# Supply.net
KiCad netlist of a schematic drawn in Altium Designer
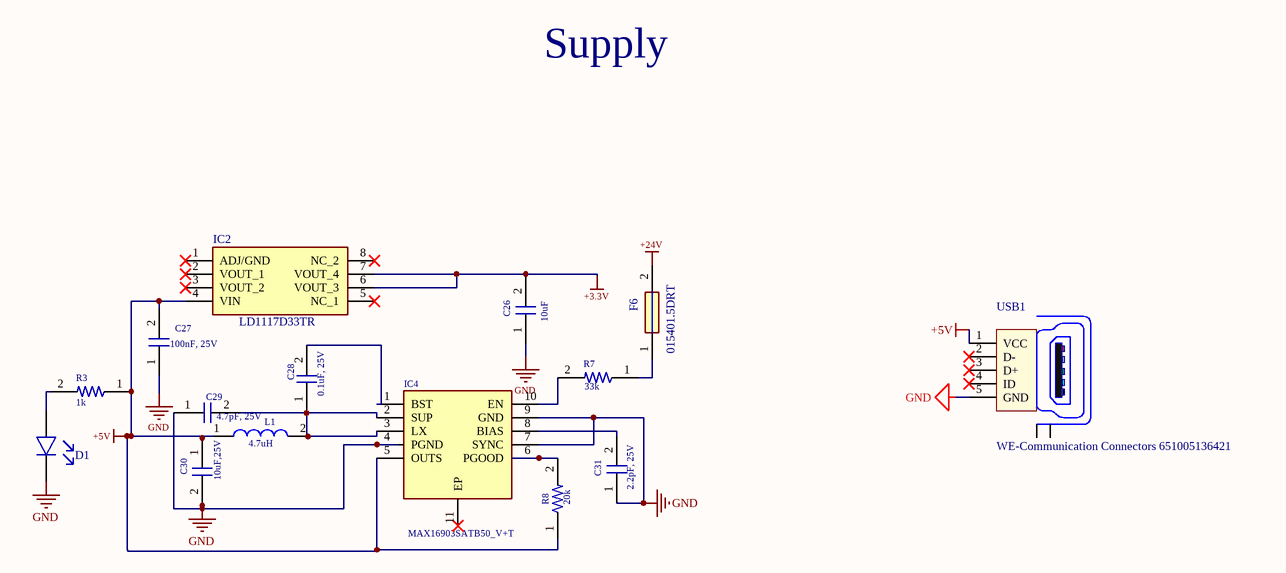
[diagram p0: Supply.SchDoc]

(export (version "E")
  (design (tool "Eeschema 10.0.6"))
  (components
    (comp (ref "C26")
      (value "10uF")
      (footprint "C 1206")
      (description "Condensador")
      (libsource (lib "MotoLibrary") (part "Condensador"))
    )
    (comp (ref "C27")
      (value "100nF, 25V")
      (footprint "C 1206")
      (description "Condensador")
      (libsource (lib "MotoLibrary") (part "Condensador"))
    )
    (comp (ref "C28")
      (value "0.1uF, 25V")
      (footprint "C 1206")
      (description "Condensador")
      (libsource (lib "MotoLibrary") (part "Condensador"))
    )
    (comp (ref "C29")
      (value "4.7pF, 25V")
      (footprint "C 1206")
      (description "Condensador")
      (libsource (lib "MotoLibrary") (part "Condensador"))
    )
    (comp (ref "C30")
      (value "10uF,25V")
      (footprint "C 1206")
      (description "Condensador")
      (libsource (lib "MotoLibrary") (part "Condensador"))
    )
    (comp (ref "C31")
      (value "2.2pF, 25V")
      (footprint "C 1206")
      (description "Condensador")
      (libsource (lib "MotoLibrary") (part "Condensador"))
    )
    (comp (ref "D1")
      (value "Valor")
      (footprint "LED 0805")
      (description "LED")
      (libsource (lib "MotoLibrary") (part "LED"))
    )
    (comp (ref "F6")
      (value "015401.5DRT")
      (footprint "Fuse Holder")
      (description "Fuse")
      (fields (field (name "MOUSER PART NUMBER") "576-015401.5DRT"))
      (libsource (lib "*") (part "015401.5DRT"))
    )
    (comp (ref "IC2")
      (value "LD1117D33TR")
      (footprint "SOIC127P600X175-8N")
      (description "Integrated Circuit")
      (fields (field (name "MOUSER PART NUMBER") "511-LD1117D33-TR"))
      (libsource (lib "*") (part "LD1117D33TR"))
    )
    (comp (ref "IC4")
      (value "MAX16903SATB50_V+T")
      (footprint "SON50P300X300X80-11N")
      (description "Integrated Circuit")
      (fields (field (name "MANUFACTURER_PART_NUMBER") "MAX16903SATB50/V+T"))
      (libsource (lib "*") (part "MAX16903SATB50_V+T"))
    )
    (comp (ref "L1")
      (value "4.7uH")
      (footprint "MPX1D0530L150")
      (description "Inductor")
      (libsource (lib "MotoLibrary") (part "Inductor"))
    )
    (comp (ref "R3")
      (value "1k")
      (footprint "R 0201")
      (description "Resistencia")
      (libsource (lib "MotoLibrary") (part "Resistencia"))
    )
    (comp (ref "R7")
      (value "33k")
      (footprint "R 0805")
      (description "Resistencia")
      (libsource (lib "MotoLibrary") (part "Resistencia"))
    )
    (comp (ref "R8")
      (value "20k")
      (footprint "R 0805")
      (description "Resistencia")
      (libsource (lib "MotoLibrary") (part "Resistencia"))
    )
    (comp (ref "USB1")
      (value "WE-Communication Connectors 651005136421")
      (footprint "65100516121")
      (description "WR-COM Mini USB Vertical TH Type B 5 Contacts")
      (fields
        (field (name "MANUFACTURER") "Würth Elektronik eiSos GmbH")
        (field (name "PARTNO") "651005136421")
        (field (name "CREATED BY") "Karrer Zheng")
      )
      (libsource (lib "651005136421_Altium_651005136421_rev16d") (part "WE-Communication Connectors 651005136421"))
    )
  )
  (nets
    (net (code "1") (name "+3.3V") (class "Default")
      (node (ref "C26") (pin "2") (pintype "passive"))
      (node (ref "IC2") (pin "6") (pinfunction "VOUT_3_6") (pintype "passive"))
      (node (ref "IC2") (pin "7") (pinfunction "VOUT_4_7") (pintype "passive"))
    )
    (net (code "2") (name "+5V") (class "Default")
      (node (ref "C27") (pin "2") (pintype "passive"))
      (node (ref "C30") (pin "1") (pintype "passive"))
      (node (ref "IC2") (pin "4") (pinfunction "VIN_4") (pintype "passive"))
      (node (ref "IC4") (pin "5") (pinfunction "OUTS_5") (pintype "passive"))
      (node (ref "L1") (pin "1") (pinfunction "1_1") (pintype "passive"))
      (node (ref "R3") (pin "1") (pinfunction "1_1") (pintype "passive"))
      (node (ref "R8") (pin "1") (pinfunction "1_1") (pintype "passive"))
      (node (ref "USB1") (pin "1") (pinfunction "VCC_1") (pintype "passive"))
    )
    (net (code "3") (name "+24V") (class "Default")
      (node (ref "F6") (pin "2") (pinfunction "2_2") (pintype "passive"))
    )
    (net (code "4") (name "GND") (class "Default")
      (node (ref "C26") (pin "1") (pintype "passive"))
      (node (ref "C27") (pin "1") (pintype "passive"))
      (node (ref "C29") (pin "1") (pintype "passive"))
      (node (ref "C30") (pin "2") (pintype "passive"))
      (node (ref "C31") (pin "1") (pintype "passive"))
      (node (ref "D1") (pin "1") (pinfunction "1_1") (pintype "passive"))
      (node (ref "IC4") (pin "4") (pinfunction "PGND_4") (pintype "passive"))
      (node (ref "IC4") (pin "7") (pinfunction "SYNC_7") (pintype "passive"))
      (node (ref "IC4") (pin "9") (pinfunction "GND_9") (pintype "passive"))
      (node (ref "USB1") (pin "5") (pinfunction "GND_5") (pintype "passive"))
    )
    (net (code "5") (name "Net-(D1-Pad2)") (class "Default")
      (node (ref "D1") (pin "2") (pinfunction "2_2") (pintype "passive"))
      (node (ref "R3") (pin "2") (pinfunction "2_2") (pintype "passive"))
    )
    (net (code "6") (name "Net-(F6-Pad1)") (class "Default")
      (node (ref "F6") (pin "1") (pinfunction "1_1") (pintype "passive"))
      (node (ref "R7") (pin "1") (pinfunction "1_1") (pintype "passive"))
    )
    (net (code "7") (name "Net-(IC4-BIAS)") (class "Default")
      (node (ref "C31") (pin "2") (pintype "passive"))
      (node (ref "IC4") (pin "8") (pinfunction "BIAS_8") (pintype "passive"))
    )
    (net (code "8") (name "Net-(IC4-BST)") (class "Default")
      (node (ref "C28") (pin "2") (pintype "passive"))
      (node (ref "IC4") (pin "1") (pinfunction "BST_1") (pintype "passive"))
    )
    (net (code "9") (name "Net-(IC4-EN)") (class "Default")
      (node (ref "IC4") (pin "10") (pinfunction "EN_10") (pintype "passive"))
      (node (ref "R7") (pin "2") (pinfunction "2_2") (pintype "passive"))
    )
    (net (code "10") (name "Net-(IC4-LX)") (class "Default")
      (node (ref "C28") (pin "1") (pintype "passive"))
      (node (ref "C29") (pin "2") (pintype "passive"))
      (node (ref "IC4") (pin "2") (pinfunction "SUP_2") (pintype "passive"))
      (node (ref "IC4") (pin "3") (pinfunction "LX_3") (pintype "passive"))
      (node (ref "L1") (pin "2") (pinfunction "2_2") (pintype "passive"))
    )
    (net (code "11") (name "Net-(IC4-PGOOD)") (class "Default")
      (node (ref "IC4") (pin "6") (pinfunction "PGOOD_6") (pintype "passive"))
      (node (ref "R8") (pin "2") (pinfunction "2_2") (pintype "passive"))
    )
    (net (code "12") (name "unconnected-(IC2-ADJ{slash}GND-Pad1)") (class "Default")
      (node (ref "IC2") (pin "1") (pinfunction "ADJ/GND_1") (pintype "passive+no_connect"))
    )
    (net (code "13") (name "unconnected-(IC2-NC_1-Pad5)") (class "Default")
      (node (ref "IC2") (pin "5") (pinfunction "NC_1_5") (pintype "passive+no_connect"))
    )
    (net (code "14") (name "unconnected-(IC2-NC_2-Pad8)") (class "Default")
      (node (ref "IC2") (pin "8") (pinfunction "NC_2_8") (pintype "passive+no_connect"))
    )
    (net (code "15") (name "unconnected-(IC2-VOUT_1-Pad2)") (class "Default")
      (node (ref "IC2") (pin "2") (pinfunction "VOUT_1_2") (pintype "passive+no_connect"))
    )
    (net (code "16") (name "unconnected-(IC2-VOUT_2-Pad3)") (class "Default")
      (node (ref "IC2") (pin "3") (pinfunction "VOUT_2_3") (pintype "passive+no_connect"))
    )
    (net (code "17") (name "unconnected-(IC4-EP-Pad11)") (class "Default")
      (node (ref "IC4") (pin "11") (pinfunction "EP_11") (pintype "passive+no_connect"))
    )
    (net (code "18") (name "unconnected-(USB1-D+-Pad3)") (class "Default")
      (node (ref "USB1") (pin "3") (pinfunction "D+_3") (pintype "passive+no_connect"))
    )
    (net (code "19") (name "unconnected-(USB1-D--Pad2)") (class "Default")
      (node (ref "USB1") (pin "2") (pinfunction "D-_2") (pintype "passive+no_connect"))
    )
    (net (code "20") (name "unconnected-(USB1-ID-Pad4)") (class "Default")
      (node (ref "USB1") (pin "4") (pinfunction "ID_4") (pintype "passive+no_connect"))
    )
    (net (code "21") (name "unconnected-(USB1-Shield-PadZ1)") (class "Default")
      (node (ref "USB1") (pin "Z1") (pinfunction "Shield_Z1") (pintype "passive"))
    )
    (net (code "22") (name "unconnected-(USB1-Shield-PadZ2)") (class "Default")
      (node (ref "USB1") (pin "Z2") (pinfunction "Shield_Z2") (pintype "passive"))
    )
  )
)
